# shieldv2.net
KiCad netlist of a schematic drawn in EAGLE
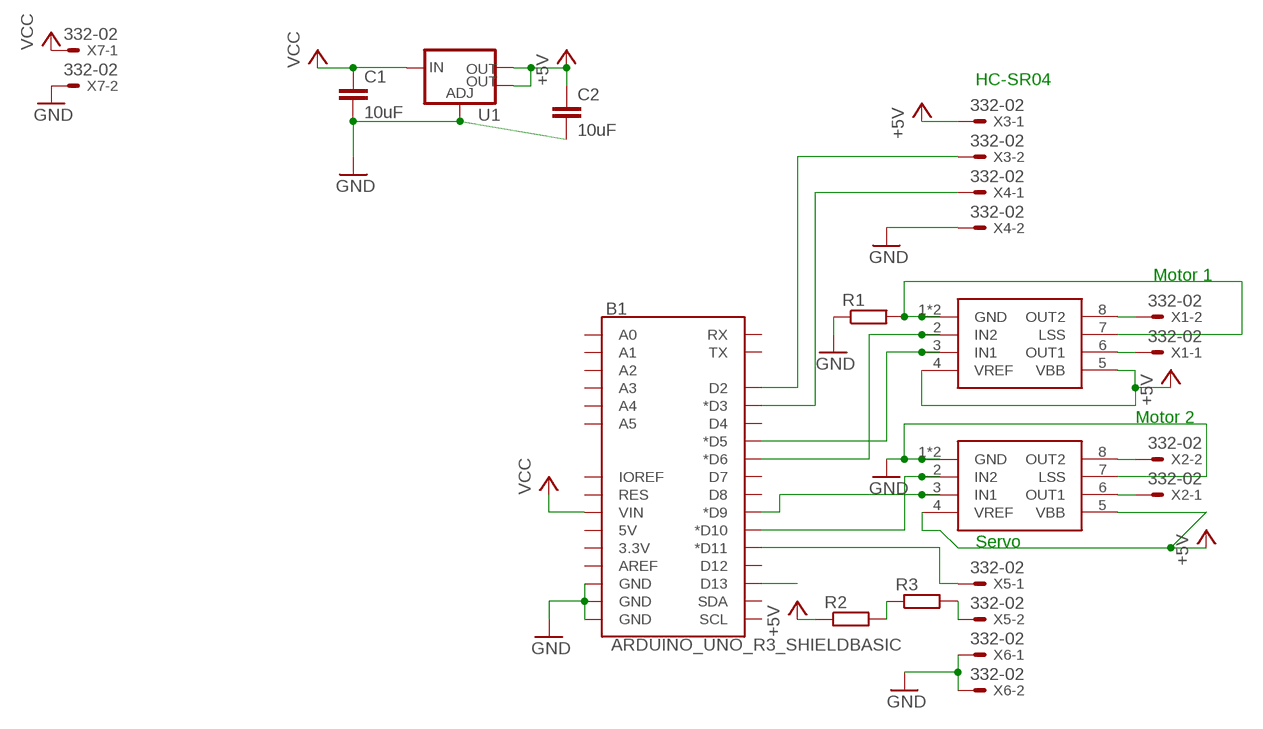
[diagram p0: schematic, sheet 1]

(export (version "E")
  (design (tool "Eeschema 10.0.6"))
  (components
    (comp (ref "B1")
      (value "ARDUINO_UNO_R3_SHIELDBASIC")
      (footprint "eagle-import:UNO_R3_SHIELD")
      (libsource (lib "eagle-import") (part "ARDUINO_UNO_R3_SHIELDBASIC"))
    )
    (comp (ref "C1")
      (value "10uF")
      (footprint "eagle-import:1206")
      (libsource (lib "eagle-import") (part "10UF-1206-6.3V-20%"))
    )
    (comp (ref "C2")
      (value "10uF")
      (footprint "eagle-import:1206")
      (libsource (lib "eagle-import") (part "10UF-1206-6.3V-20%"))
    )
    (comp (ref "R1")
      (value "R-EU_M1206")
      (footprint "eagle-import:M1206")
      (libsource (lib "eagle-import") (part "R-EU_M1206"))
    )
    (comp (ref "R2")
      (value "R-EU_M1206")
      (footprint "eagle-import:M1206")
      (libsource (lib "eagle-import") (part "R-EU_M1206"))
    )
    (comp (ref "R3")
      (value "R-EU_M1206")
      (footprint "eagle-import:M1206")
      (libsource (lib "eagle-import") (part "R-EU_M1206"))
    )
    (comp (ref "U$1")
      (value "A4953-H-BRIDGE-MOTOR-DRIVER-PAD")
      (footprint "eagle-import:SOIC8_PAD")
      (libsource (lib "eagle-import") (part "A4953-H-BRIDGE-MOTOR-DRIVER-PAD"))
    )
    (comp (ref "U$2")
      (value "A4953-H-BRIDGE-MOTOR-DRIVER-PAD")
      (footprint "eagle-import:SOIC8_PAD")
      (libsource (lib "eagle-import") (part "A4953-H-BRIDGE-MOTOR-DRIVER-PAD"))
    )
    (comp (ref "U1")
      (value "V_REG_LM1117SOT223")
      (footprint "eagle-import:SOT223")
      (libsource (lib "eagle-import") (part "V_REG_LM1117SOT223"))
    )
    (comp (ref "X1")
      (value "332-02")
      (footprint "eagle-import:332-02")
      (libsource (lib "eagle-import") (part "332-02"))
    )
    (comp (ref "X2")
      (value "332-02")
      (footprint "eagle-import:332-02")
      (libsource (lib "eagle-import") (part "332-02"))
    )
    (comp (ref "X3")
      (value "332-02")
      (footprint "eagle-import:332-02")
      (libsource (lib "eagle-import") (part "332-02"))
    )
    (comp (ref "X4")
      (value "332-02")
      (footprint "eagle-import:332-02")
      (libsource (lib "eagle-import") (part "332-02"))
    )
    (comp (ref "X5")
      (value "332-02")
      (footprint "eagle-import:332-02")
      (libsource (lib "eagle-import") (part "332-02"))
    )
    (comp (ref "X6")
      (value "332-02")
      (footprint "eagle-import:332-02")
      (libsource (lib "eagle-import") (part "332-02"))
    )
    (comp (ref "X7")
      (value "332-02")
      (footprint "eagle-import:332-02")
      (libsource (lib "eagle-import") (part "332-02"))
    )
  )
  (nets
    (net (code "1") (name "+5V") (class "Default")
      (node (ref "C2") (pin "1") (pinfunction "1_1") (pintype "passive"))
      (node (ref "R2") (pin "1") (pinfunction "1_1") (pintype "passive"))
      (node (ref "U$1") (pin "4") (pinfunction "VREF_4") (pintype "bidirectional"))
      (node (ref "U$1") (pin "5") (pinfunction "VBB_5") (pintype "bidirectional"))
      (node (ref "U$2") (pin "4") (pinfunction "VREF_4") (pintype "bidirectional"))
      (node (ref "U$2") (pin "5") (pinfunction "VBB_5") (pintype "bidirectional"))
      (node (ref "U1") (pin "2") (pinfunction "OUT_2") (pintype "output"))
      (node (ref "U1") (pin "4") (pinfunction "OUT_4") (pintype "output"))
      (node (ref "X3") (pin "1") (pinfunction "S_1") (pintype "passive"))
    )
    (net (code "2") (name "GND") (class "Default")
      (node (ref "B1") (pin "GND@0") (pinfunction "GND_GND@0") (pintype "bidirectional"))
      (node (ref "B1") (pin "GND@1") (pinfunction "GND_GND@1") (pintype "bidirectional"))
      (node (ref "B1") (pin "GND@2") (pinfunction "GND_GND@2") (pintype "bidirectional"))
      (node (ref "C1") (pin "2") (pinfunction "2_2") (pintype "passive"))
      (node (ref "C2") (pin "2") (pinfunction "2_2") (pintype "passive"))
      (node (ref "R1") (pin "1") (pinfunction "1_1") (pintype "passive"))
      (node (ref "U$2") (pin "1") (pinfunction "GND_1") (pintype "bidirectional"))
      (node (ref "U$2") (pin "7") (pinfunction "LSS_7") (pintype "bidirectional"))
      (node (ref "U$2") (pin "GND") (pinfunction "GND_GND") (pintype "bidirectional"))
      (node (ref "U1") (pin "1") (pinfunction "ADJ_1") (pintype "input"))
      (node (ref "X4") (pin "2") (pinfunction "S_2") (pintype "passive"))
      (node (ref "X6") (pin "1") (pinfunction "S_1") (pintype "passive"))
      (node (ref "X6") (pin "2") (pinfunction "S_2") (pintype "passive"))
      (node (ref "X7") (pin "2") (pinfunction "S_2") (pintype "passive"))
    )
    (net (code "3") (name "Net-(B1-*D3)") (class "Default")
      (node (ref "B1") (pin "D3") (pinfunction "*D3_D3") (pintype "bidirectional"))
      (node (ref "X4") (pin "1") (pinfunction "S_1") (pintype "passive"))
    )
    (net (code "4") (name "Net-(B1-*D5)") (class "Default")
      (node (ref "B1") (pin "D5") (pinfunction "*D5_D5") (pintype "bidirectional"))
      (node (ref "U$1") (pin "3") (pinfunction "IN1_3") (pintype "bidirectional"))
    )
    (net (code "5") (name "Net-(B1-*D6)") (class "Default")
      (node (ref "B1") (pin "D6") (pinfunction "*D6_D6") (pintype "bidirectional"))
      (node (ref "U$1") (pin "2") (pinfunction "IN2_2") (pintype "bidirectional"))
    )
    (net (code "6") (name "Net-(B1-*D9)") (class "Default")
      (node (ref "B1") (pin "D9") (pinfunction "*D9_D9") (pintype "bidirectional"))
      (node (ref "U$2") (pin "3") (pinfunction "IN1_3") (pintype "bidirectional"))
    )
    (net (code "7") (name "Net-(B1-*D10)") (class "Default")
      (node (ref "B1") (pin "D10") (pinfunction "*D10_D10") (pintype "bidirectional"))
      (node (ref "U$2") (pin "2") (pinfunction "IN2_2") (pintype "bidirectional"))
    )
    (net (code "8") (name "Net-(B1-*D11)") (class "Default")
      (node (ref "B1") (pin "D11") (pinfunction "*D11_D11") (pintype "bidirectional"))
      (node (ref "X5") (pin "1") (pinfunction "S_1") (pintype "passive"))
    )
    (net (code "9") (name "Net-(R2-Pad2)") (class "Default")
      (node (ref "R2") (pin "2") (pinfunction "2_2") (pintype "passive"))
      (node (ref "R3") (pin "1") (pinfunction "1_1") (pintype "passive"))
    )
    (net (code "10") (name "Net-(U$1-LSS)") (class "Default")
      (node (ref "R1") (pin "2") (pinfunction "2_2") (pintype "passive"))
      (node (ref "U$1") (pin "1") (pinfunction "GND_1") (pintype "bidirectional"))
      (node (ref "U$1") (pin "7") (pinfunction "LSS_7") (pintype "bidirectional"))
      (node (ref "U$1") (pin "GND") (pinfunction "GND_GND") (pintype "bidirectional"))
    )
    (net (code "11") (name "Net-(U$1-OUT1)") (class "Default")
      (node (ref "U$1") (pin "6") (pinfunction "OUT1_6") (pintype "bidirectional"))
      (node (ref "X1") (pin "1") (pinfunction "S_1") (pintype "passive"))
    )
    (net (code "12") (name "Net-(U$1-OUT2)") (class "Default")
      (node (ref "U$1") (pin "8") (pinfunction "OUT2_8") (pintype "bidirectional"))
      (node (ref "X1") (pin "2") (pinfunction "S_2") (pintype "passive"))
    )
    (net (code "13") (name "Net-(U$2-OUT1)") (class "Default")
      (node (ref "U$2") (pin "6") (pinfunction "OUT1_6") (pintype "bidirectional"))
      (node (ref "X2") (pin "1") (pinfunction "S_1") (pintype "passive"))
    )
    (net (code "14") (name "Net-(U$2-OUT2)") (class "Default")
      (node (ref "U$2") (pin "8") (pinfunction "OUT2_8") (pintype "bidirectional"))
      (node (ref "X2") (pin "2") (pinfunction "S_2") (pintype "passive"))
    )
    (net (code "15") (name "Net-(X3B-S)") (class "Default")
      (node (ref "B1") (pin "D2") (pinfunction "D2_D2") (pintype "bidirectional"))
      (node (ref "X3") (pin "2") (pinfunction "S_2") (pintype "passive"))
    )
    (net (code "16") (name "Net-(X5B-S)") (class "Default")
      (node (ref "R3") (pin "2") (pinfunction "2_2") (pintype "passive"))
      (node (ref "X5") (pin "2") (pinfunction "S_2") (pintype "passive"))
    )
    (net (code "17") (name "VCC") (class "Default")
      (node (ref "B1") (pin "VIN") (pinfunction "VIN_VIN") (pintype "bidirectional"))
      (node (ref "C1") (pin "1") (pinfunction "1_1") (pintype "passive"))
      (node (ref "U1") (pin "3") (pinfunction "IN_3") (pintype "input"))
      (node (ref "X7") (pin "1") (pinfunction "S_1") (pintype "passive"))
    )
    (net (code "18") (name "unconnected-(B1-Pad3.3V)") (class "Default")
      (node (ref "B1") (pin "3.3V") (pinfunction "3.3V_3.3V") (pintype "bidirectional"))
    )
    (net (code "19") (name "unconnected-(B1-Pad5V)") (class "Default")
      (node (ref "B1") (pin "5V") (pinfunction "5V_5V") (pintype "bidirectional"))
    )
    (net (code "20") (name "unconnected-(B1-PadA0)") (class "Default")
      (node (ref "B1") (pin "A0") (pinfunction "A0_A0") (pintype "bidirectional"))
    )
    (net (code "21") (name "unconnected-(B1-PadA1)") (class "Default")
      (node (ref "B1") (pin "A1") (pinfunction "A1_A1") (pintype "bidirectional"))
    )
    (net (code "22") (name "unconnected-(B1-PadA2)") (class "Default")
      (node (ref "B1") (pin "A2") (pinfunction "A2_A2") (pintype "bidirectional"))
    )
    (net (code "23") (name "unconnected-(B1-PadA3)") (class "Default")
      (node (ref "B1") (pin "A3") (pinfunction "A3_A3") (pintype "bidirectional"))
    )
    (net (code "24") (name "unconnected-(B1-PadA4)") (class "Default")
      (node (ref "B1") (pin "A4") (pinfunction "A4_A4") (pintype "bidirectional"))
    )
    (net (code "25") (name "unconnected-(B1-PadA5)") (class "Default")
      (node (ref "B1") (pin "A5") (pinfunction "A5_A5") (pintype "bidirectional"))
    )
    (net (code "26") (name "unconnected-(B1-PadAREF)") (class "Default")
      (node (ref "B1") (pin "AREF") (pinfunction "AREF_AREF") (pintype "bidirectional"))
    )
    (net (code "27") (name "unconnected-(B1-PadD4)") (class "Default")
      (node (ref "B1") (pin "D4") (pinfunction "D4_D4") (pintype "bidirectional"))
    )
    (net (code "28") (name "unconnected-(B1-PadD7)") (class "Default")
      (node (ref "B1") (pin "D7") (pinfunction "D7_D7") (pintype "bidirectional"))
    )
    (net (code "29") (name "unconnected-(B1-PadD8)") (class "Default")
      (node (ref "B1") (pin "D8") (pinfunction "D8_D8") (pintype "bidirectional"))
    )
    (net (code "30") (name "unconnected-(B1-PadD12)") (class "Default")
      (node (ref "B1") (pin "D12") (pinfunction "D12_D12") (pintype "bidirectional"))
    )
    (net (code "31") (name "unconnected-(B1-PadD13)") (class "Default")
      (node (ref "B1") (pin "D13") (pinfunction "D13_D13") (pintype "bidirectional"))
    )
    (net (code "32") (name "unconnected-(B1-PadIOREF)") (class "Default")
      (node (ref "B1") (pin "IOREF") (pinfunction "IOREF_IOREF") (pintype "bidirectional"))
    )
    (net (code "33") (name "unconnected-(B1-PadRES)") (class "Default")
      (node (ref "B1") (pin "RES") (pinfunction "RES_RES") (pintype "bidirectional"))
    )
    (net (code "34") (name "unconnected-(B1-PadRX)") (class "Default")
      (node (ref "B1") (pin "RX") (pinfunction "RX_RX") (pintype "bidirectional"))
    )
    (net (code "35") (name "unconnected-(B1-PadSCL)") (class "Default")
      (node (ref "B1") (pin "SCL") (pinfunction "SCL_SCL") (pintype "bidirectional"))
    )
    (net (code "36") (name "unconnected-(B1-PadSDA)") (class "Default")
      (node (ref "B1") (pin "SDA") (pinfunction "SDA_SDA") (pintype "bidirectional"))
    )
    (net (code "37") (name "unconnected-(B1-PadTX)") (class "Default")
      (node (ref "B1") (pin "TX") (pinfunction "TX_TX") (pintype "bidirectional"))
    )
  )
)
